# analog.net
KiCad netlist of a schematic drawn in EAGLE
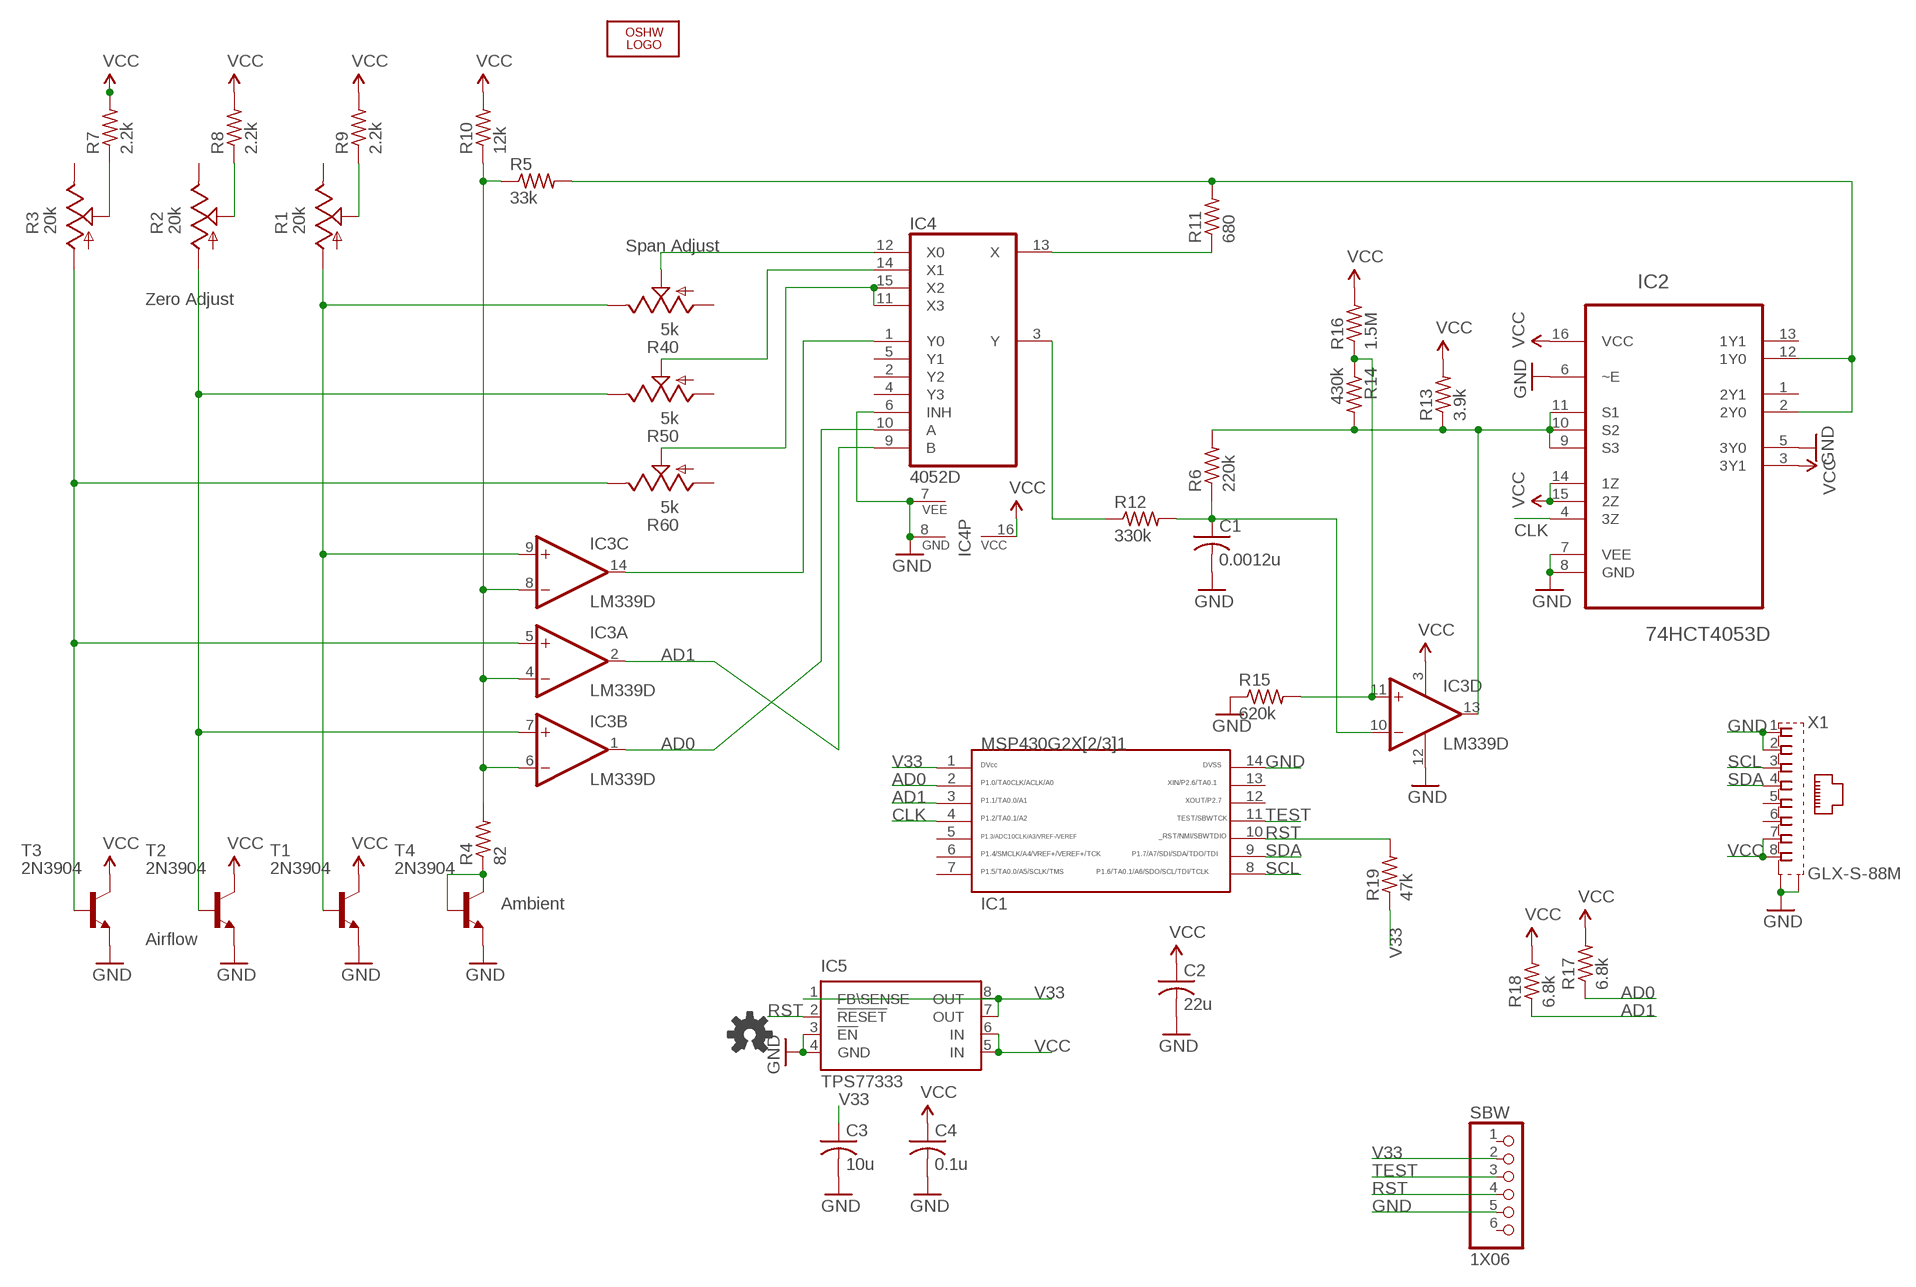
[diagram p0: schematic, sheet 1]

(export (version "E")
  (design (tool "Eeschema 10.0.6"))
  (components
    (comp (ref "C1")
      (value "0.0012u")
      (footprint "eagle-import:C0805")
      (libsource (lib "eagle-import") (part "C-USC0805"))
    )
    (comp (ref "C2")
      (value "22u")
      (footprint "eagle-import:C0805")
      (libsource (lib "eagle-import") (part "C-USC0805"))
    )
    (comp (ref "C3")
      (value "10u")
      (footprint "eagle-import:C0805")
      (libsource (lib "eagle-import") (part "C-USC0805"))
    )
    (comp (ref "C4")
      (value "0.1u")
      (footprint "eagle-import:C0805")
      (libsource (lib "eagle-import") (part "C-USC0805"))
    )
    (comp (ref "IC1")
      (value "G2X[2/3]1---PW14")
      (footprint "eagle-import:PW14")
      (libsource (lib "eagle-import") (part "G2X[2/3]1---PW14"))
    )
    (comp (ref "IC2")
      (value "74HCT4053D")
      (footprint "eagle-import:SOIC127P600X175-16N")
      (libsource (lib "eagle-import") (part "74HCT4053D"))
    )
    (comp (ref "IC3")
      (value "LM339D")
      (footprint "eagle-import:SO14")
      (libsource (lib "eagle-import") (part "LM339D"))
    )
    (comp (ref "IC4")
      (value "4052D")
      (footprint "eagle-import:SO16")
      (libsource (lib "eagle-import") (part "4052D"))
    )
    (comp (ref "IC5")
      (value "TPS77333")
      (footprint "eagle-import:TPS77333")
      (libsource (lib "eagle-import") (part "TPS77333"))
    )
    (comp (ref "LOGO1")
      (value "OSHW_LOGO_FILLX0150-NT")
      (footprint "eagle-import:OSHW_FILLX150_NOTEXT")
      (libsource (lib "eagle-import") (part "OSHW_LOGO_FILLX0150-NT"))
    )
    (comp (ref "R1")
      (value "20k")
      (footprint "eagle-import:SM-42_43W")
      (libsource (lib "eagle-import") (part "TRIM_US-SM-42/43W"))
    )
    (comp (ref "R2")
      (value "20k")
      (footprint "eagle-import:SM-42_43W")
      (libsource (lib "eagle-import") (part "TRIM_US-SM-42/43W"))
    )
    (comp (ref "R3")
      (value "20k")
      (footprint "eagle-import:SM-42_43W")
      (libsource (lib "eagle-import") (part "TRIM_US-SM-42/43W"))
    )
    (comp (ref "R4")
      (value "82")
      (footprint "eagle-import:M0805")
      (libsource (lib "eagle-import") (part "R-US_M0805"))
    )
    (comp (ref "R5")
      (value "33k")
      (footprint "eagle-import:R0805")
      (libsource (lib "eagle-import") (part "R-US_R0805"))
    )
    (comp (ref "R6")
      (value "220k")
      (footprint "eagle-import:R0805")
      (libsource (lib "eagle-import") (part "R-US_R0805"))
    )
    (comp (ref "R7")
      (value "2.2k")
      (footprint "eagle-import:M0805")
      (libsource (lib "eagle-import") (part "resistor_R-US_M0805"))
    )
    (comp (ref "R8")
      (value "2.2k")
      (footprint "eagle-import:R0805")
      (libsource (lib "eagle-import") (part "R-US_R0805"))
    )
    (comp (ref "R9")
      (value "2.2k")
      (footprint "eagle-import:R0805")
      (libsource (lib "eagle-import") (part "R-US_R0805"))
    )
    (comp (ref "R10")
      (value "12k")
      (footprint "eagle-import:R0805")
      (libsource (lib "eagle-import") (part "R-US_R0805"))
    )
    (comp (ref "R11")
      (value "680")
      (footprint "eagle-import:R0805")
      (libsource (lib "eagle-import") (part "R-US_R0805"))
    )
    (comp (ref "R12")
      (value "330k")
      (footprint "eagle-import:R0805")
      (libsource (lib "eagle-import") (part "R-US_R0805"))
    )
    (comp (ref "R13")
      (value "3.9k")
      (footprint "eagle-import:R0805")
      (libsource (lib "eagle-import") (part "R-US_R0805"))
    )
    (comp (ref "R14")
      (value "430k")
      (footprint "eagle-import:R0805")
      (libsource (lib "eagle-import") (part "R-US_R0805"))
    )
    (comp (ref "R15")
      (value "620k")
      (footprint "eagle-import:R0805")
      (libsource (lib "eagle-import") (part "R-US_R0805"))
    )
    (comp (ref "R16")
      (value "1.5M")
      (footprint "eagle-import:R0805")
      (libsource (lib "eagle-import") (part "R-US_R0805"))
    )
    (comp (ref "R17")
      (value "6.8k")
      (footprint "eagle-import:M0805")
      (libsource (lib "eagle-import") (part "R-US_M0805"))
    )
    (comp (ref "R18")
      (value "6.8k")
      (footprint "eagle-import:M0805")
      (libsource (lib "eagle-import") (part "R-US_M0805"))
    )
    (comp (ref "R19")
      (value "47k")
      (footprint "eagle-import:R0805")
      (libsource (lib "eagle-import") (part "R-US_R0805"))
    )
    (comp (ref "R40")
      (value "5k")
      (footprint "eagle-import:SM-42_43W")
      (libsource (lib "eagle-import") (part "TRIM_US-SM-42/43W"))
    )
    (comp (ref "R50")
      (value "5k")
      (footprint "eagle-import:SM-42_43W")
      (libsource (lib "eagle-import") (part "TRIM_US-SM-42/43W"))
    )
    (comp (ref "R60")
      (value "5k")
      (footprint "eagle-import:SM-42_43W")
      (libsource (lib "eagle-import") (part "TRIM_US-SM-42/43W"))
    )
    (comp (ref "SBW")
      (value "1X06")
      (footprint "eagle-import:1X06")
      (libsource (lib "eagle-import") (part "1X06"))
    )
    (comp (ref "T1")
      (value "2N3904")
      (footprint "eagle-import:TO92")
      (libsource (lib "eagle-import") (part "2N3904"))
    )
    (comp (ref "T2")
      (value "2N3904")
      (footprint "eagle-import:TO92")
      (libsource (lib "eagle-import") (part "2N3904"))
    )
    (comp (ref "T3")
      (value "2N3904")
      (footprint "eagle-import:TO92")
      (libsource (lib "eagle-import") (part "2N3904"))
    )
    (comp (ref "T4")
      (value "2N3904")
      (footprint "eagle-import:TO92")
      (libsource (lib "eagle-import") (part "2N3904"))
    )
    (comp (ref "X1")
      (value "GLX-S-88M")
      (footprint "eagle-import:GLX-S-88M")
      (libsource (lib "eagle-import") (part "GLX-S-88M"))
    )
  )
  (nets
    (net (code "1") (name "/AD0") (class "Default")
      (node (ref "IC1") (pin "2") (pinfunction "2_2") (pintype "bidirectional"))
      (node (ref "IC3") (pin "1") (pinfunction "OUT_1") (pintype "open_collector"))
      (node (ref "IC4") (pin "10") (pinfunction "A_10") (pintype "input"))
      (node (ref "R17") (pin "1") (pinfunction "1_1") (pintype "passive"))
    )
    (net (code "2") (name "/AD1") (class "Default")
      (node (ref "IC1") (pin "3") (pinfunction "3_3") (pintype "bidirectional"))
      (node (ref "IC3") (pin "2") (pinfunction "OUT_2") (pintype "open_collector"))
      (node (ref "IC4") (pin "9") (pinfunction "B_9") (pintype "input"))
      (node (ref "R18") (pin "1") (pinfunction "1_1") (pintype "passive"))
    )
    (net (code "3") (name "/CLK") (class "Default")
      (node (ref "IC1") (pin "4") (pinfunction "4_4") (pintype "bidirectional"))
      (node (ref "IC2") (pin "4") (pinfunction "3Z_4") (pintype "bidirectional"))
    )
    (net (code "4") (name "/RST") (class "Default")
      (node (ref "IC1") (pin "10") (pinfunction "10_10") (pintype "bidirectional"))
      (node (ref "IC5") (pin "2") (pinfunction "~{RESET}_2") (pintype "input"))
      (node (ref "R19") (pin "2") (pinfunction "2_2") (pintype "passive"))
      (node (ref "SBW") (pin "4") (pinfunction "4_4") (pintype "passive"))
    )
    (net (code "5") (name "/SCL") (class "Default")
      (node (ref "IC1") (pin "8") (pinfunction "8_8") (pintype "bidirectional"))
      (node (ref "X1") (pin "3") (pinfunction "3_3") (pintype "passive"))
    )
    (net (code "6") (name "/SDA") (class "Default")
      (node (ref "IC1") (pin "9") (pinfunction "9_9") (pintype "bidirectional"))
      (node (ref "X1") (pin "4") (pinfunction "4_4") (pintype "passive"))
    )
    (net (code "7") (name "/TEST") (class "Default")
      (node (ref "IC1") (pin "11") (pinfunction "11_11") (pintype "bidirectional"))
      (node (ref "SBW") (pin "3") (pinfunction "3_3") (pintype "passive"))
    )
    (net (code "8") (name "/V33") (class "Default")
      (node (ref "C3") (pin "1") (pinfunction "1_1") (pintype "passive"))
      (node (ref "IC1") (pin "1") (pinfunction "1_1") (pintype "bidirectional"))
      (node (ref "IC5") (pin "1") (pinfunction "FB\\SENSE_1") (pintype "input"))
      (node (ref "IC5") (pin "7") (pinfunction "OUT_7") (pintype "output"))
      (node (ref "IC5") (pin "8") (pinfunction "OUT_8") (pintype "passive"))
      (node (ref "R19") (pin "1") (pinfunction "1_1") (pintype "passive"))
      (node (ref "SBW") (pin "2") (pinfunction "2_2") (pintype "passive"))
    )
    (net (code "9") (name "GND") (class "Default")
      (node (ref "C1") (pin "2") (pinfunction "2_2") (pintype "passive"))
      (node (ref "C2") (pin "2") (pinfunction "2_2") (pintype "passive"))
      (node (ref "C3") (pin "2") (pinfunction "2_2") (pintype "passive"))
      (node (ref "C4") (pin "2") (pinfunction "2_2") (pintype "passive"))
      (node (ref "IC1") (pin "14") (pinfunction "14_14") (pintype "bidirectional"))
      (node (ref "IC2") (pin "5") (pinfunction "3Y0_5") (pintype "bidirectional"))
      (node (ref "IC2") (pin "6") (pinfunction "~{E}_6") (pintype "input"))
      (node (ref "IC2") (pin "7") (pinfunction "VEE_7") (pintype "power_in"))
      (node (ref "IC2") (pin "8") (pinfunction "GND_8") (pintype "passive"))
      (node (ref "IC3") (pin "12") (pinfunction "GND_12") (pintype "power_in"))
      (node (ref "IC4") (pin "6") (pinfunction "INH_6") (pintype "input"))
      (node (ref "IC4") (pin "7") (pinfunction "VEE_7") (pintype "power_in"))
      (node (ref "IC4") (pin "8") (pinfunction "GND_8") (pintype "power_in"))
      (node (ref "IC5") (pin "3") (pinfunction "~{EN}_3") (pintype "input"))
      (node (ref "IC5") (pin "4") (pinfunction "GND_4") (pintype "power_in"))
      (node (ref "R15") (pin "1") (pinfunction "1_1") (pintype "passive"))
      (node (ref "SBW") (pin "5") (pinfunction "5_5") (pintype "passive"))
      (node (ref "T1") (pin "3") (pinfunction "E_3") (pintype "passive"))
      (node (ref "T2") (pin "3") (pinfunction "E_3") (pintype "passive"))
      (node (ref "T3") (pin "3") (pinfunction "E_3") (pintype "passive"))
      (node (ref "T4") (pin "3") (pinfunction "E_3") (pintype "passive"))
      (node (ref "X1") (pin "1") (pinfunction "1_1") (pintype "passive"))
      (node (ref "X1") (pin "2") (pinfunction "2_2") (pintype "passive"))
      (node (ref "X1") (pin "S1") (pinfunction "S1_S1") (pintype "passive"))
      (node (ref "X1") (pin "S2") (pinfunction "S2_S2") (pintype "passive"))
    )
    (net (code "10") (name "Net-(IC2-1Y0)") (class "Default")
      (node (ref "IC2") (pin "12") (pinfunction "1Y0_12") (pintype "bidirectional"))
      (node (ref "IC2") (pin "2") (pinfunction "2Y0_2") (pintype "bidirectional"))
      (node (ref "R11") (pin "2") (pinfunction "2_2") (pintype "passive"))
      (node (ref "R5") (pin "2") (pinfunction "2_2") (pintype "passive"))
    )
    (net (code "11") (name "Net-(IC2-S1)") (class "Default")
      (node (ref "IC2") (pin "10") (pinfunction "S2_10") (pintype "input"))
      (node (ref "IC2") (pin "11") (pinfunction "S1_11") (pintype "input"))
      (node (ref "IC2") (pin "9") (pinfunction "S3_9") (pintype "input"))
      (node (ref "IC3") (pin "13") (pinfunction "OUT_13") (pintype "open_collector"))
      (node (ref "R13") (pin "1") (pinfunction "1_1") (pintype "passive"))
      (node (ref "R14") (pin "2") (pinfunction "2_2") (pintype "passive"))
      (node (ref "R6") (pin "2") (pinfunction "2_2") (pintype "passive"))
    )
    (net (code "12") (name "Net-(IC3A-+IN)") (class "Default")
      (node (ref "IC3") (pin "5") (pinfunction "+IN_5") (pintype "input"))
      (node (ref "R3") (pin "1") (pinfunction "A_1") (pintype "passive"))
      (node (ref "R60") (pin "3") (pinfunction "E_3") (pintype "passive"))
      (node (ref "T3") (pin "2") (pinfunction "B_2") (pintype "passive"))
    )
    (net (code "13") (name "Net-(IC3A--IN)") (class "Default")
      (node (ref "IC3") (pin "4") (pinfunction "-IN_4") (pintype "input"))
      (node (ref "IC3") (pin "6") (pinfunction "-IN_6") (pintype "input"))
      (node (ref "IC3") (pin "8") (pinfunction "-IN_8") (pintype "input"))
      (node (ref "R10") (pin "1") (pinfunction "1_1") (pintype "passive"))
      (node (ref "R4") (pin "2") (pinfunction "2_2") (pintype "passive"))
      (node (ref "R5") (pin "1") (pinfunction "1_1") (pintype "passive"))
    )
    (net (code "14") (name "Net-(IC3B-+IN)") (class "Default")
      (node (ref "IC3") (pin "7") (pinfunction "+IN_7") (pintype "input"))
      (node (ref "R2") (pin "1") (pinfunction "A_1") (pintype "passive"))
      (node (ref "R50") (pin "3") (pinfunction "E_3") (pintype "passive"))
      (node (ref "T2") (pin "2") (pinfunction "B_2") (pintype "passive"))
    )
    (net (code "15") (name "Net-(IC3C-+IN)") (class "Default")
      (node (ref "IC3") (pin "9") (pinfunction "+IN_9") (pintype "input"))
      (node (ref "R1") (pin "1") (pinfunction "A_1") (pintype "passive"))
      (node (ref "R40") (pin "3") (pinfunction "E_3") (pintype "passive"))
      (node (ref "T1") (pin "2") (pinfunction "B_2") (pintype "passive"))
    )
    (net (code "16") (name "Net-(IC3C-OUT)") (class "Default")
      (node (ref "IC3") (pin "14") (pinfunction "OUT_14") (pintype "open_collector"))
      (node (ref "IC4") (pin "1") (pinfunction "Y0_1") (pintype "bidirectional"))
    )
    (net (code "17") (name "Net-(IC3D-+IN)") (class "Default")
      (node (ref "IC3") (pin "11") (pinfunction "+IN_11") (pintype "input"))
      (node (ref "R14") (pin "1") (pinfunction "1_1") (pintype "passive"))
      (node (ref "R15") (pin "2") (pinfunction "2_2") (pintype "passive"))
      (node (ref "R16") (pin "1") (pinfunction "1_1") (pintype "passive"))
    )
    (net (code "18") (name "Net-(IC3D--IN)") (class "Default")
      (node (ref "C1") (pin "1") (pinfunction "1_1") (pintype "passive"))
      (node (ref "IC3") (pin "10") (pinfunction "-IN_10") (pintype "input"))
      (node (ref "R12") (pin "2") (pinfunction "2_2") (pintype "passive"))
      (node (ref "R6") (pin "1") (pinfunction "1_1") (pintype "passive"))
    )
    (net (code "19") (name "Net-(IC4A-X)") (class "Default")
      (node (ref "IC4") (pin "13") (pinfunction "X_13") (pintype "bidirectional"))
      (node (ref "R11") (pin "1") (pinfunction "1_1") (pintype "passive"))
    )
    (net (code "20") (name "Net-(IC4A-X0)") (class "Default")
      (node (ref "IC4") (pin "12") (pinfunction "X0_12") (pintype "bidirectional"))
      (node (ref "R40") (pin "2") (pinfunction "S_2") (pintype "passive"))
    )
    (net (code "21") (name "Net-(IC4A-X1)") (class "Default")
      (node (ref "IC4") (pin "14") (pinfunction "X1_14") (pintype "bidirectional"))
      (node (ref "R50") (pin "2") (pinfunction "S_2") (pintype "passive"))
    )
    (net (code "22") (name "Net-(IC4A-X2)") (class "Default")
      (node (ref "IC4") (pin "11") (pinfunction "X3_11") (pintype "bidirectional"))
      (node (ref "IC4") (pin "15") (pinfunction "X2_15") (pintype "bidirectional"))
      (node (ref "R60") (pin "2") (pinfunction "S_2") (pintype "passive"))
    )
    (net (code "23") (name "Net-(IC4A-Y)") (class "Default")
      (node (ref "IC4") (pin "3") (pinfunction "Y_3") (pintype "bidirectional"))
      (node (ref "R12") (pin "1") (pinfunction "1_1") (pintype "passive"))
    )
    (net (code "24") (name "Net-(R1-S)") (class "Default")
      (node (ref "R1") (pin "2") (pinfunction "S_2") (pintype "passive"))
      (node (ref "R9") (pin "1") (pinfunction "1_1") (pintype "passive"))
    )
    (net (code "25") (name "Net-(R2-S)") (class "Default")
      (node (ref "R2") (pin "2") (pinfunction "S_2") (pintype "passive"))
      (node (ref "R8") (pin "1") (pinfunction "1_1") (pintype "passive"))
    )
    (net (code "26") (name "Net-(R3-S)") (class "Default")
      (node (ref "R3") (pin "2") (pinfunction "S_2") (pintype "passive"))
      (node (ref "R7") (pin "1") (pinfunction "1_1") (pintype "passive"))
    )
    (net (code "27") (name "Net-(T4-B)") (class "Default")
      (node (ref "R4") (pin "1") (pinfunction "1_1") (pintype "passive"))
      (node (ref "T4") (pin "1") (pinfunction "C_1") (pintype "passive"))
      (node (ref "T4") (pin "2") (pinfunction "B_2") (pintype "passive"))
    )
    (net (code "28") (name "VCC") (class "Default")
      (node (ref "C2") (pin "1") (pinfunction "1_1") (pintype "passive"))
      (node (ref "C4") (pin "1") (pinfunction "1_1") (pintype "passive"))
      (node (ref "IC2") (pin "14") (pinfunction "1Z_14") (pintype "bidirectional"))
      (node (ref "IC2") (pin "15") (pinfunction "2Z_15") (pintype "bidirectional"))
      (node (ref "IC2") (pin "16") (pinfunction "VCC_16") (pintype "power_in"))
      (node (ref "IC2") (pin "3") (pinfunction "3Y1_3") (pintype "bidirectional"))
      (node (ref "IC3") (pin "3") (pinfunction "V+_3") (pintype "power_in"))
      (node (ref "IC4") (pin "16") (pinfunction "VCC_16") (pintype "power_in"))
      (node (ref "IC5") (pin "5") (pinfunction "IN_5") (pintype "input"))
      (node (ref "IC5") (pin "6") (pinfunction "IN_6") (pintype "input"))
      (node (ref "R10") (pin "2") (pinfunction "2_2") (pintype "passive"))
      (node (ref "R13") (pin "2") (pinfunction "2_2") (pintype "passive"))
      (node (ref "R16") (pin "2") (pinfunction "2_2") (pintype "passive"))
      (node (ref "R17") (pin "2") (pinfunction "2_2") (pintype "passive"))
      (node (ref "R18") (pin "2") (pinfunction "2_2") (pintype "passive"))
      (node (ref "R7") (pin "2") (pinfunction "2_2") (pintype "passive"))
      (node (ref "R8") (pin "2") (pinfunction "2_2") (pintype "passive"))
      (node (ref "R9") (pin "2") (pinfunction "2_2") (pintype "passive"))
      (node (ref "T1") (pin "1") (pinfunction "C_1") (pintype "passive"))
      (node (ref "T2") (pin "1") (pinfunction "C_1") (pintype "passive"))
      (node (ref "T3") (pin "1") (pinfunction "C_1") (pintype "passive"))
      (node (ref "X1") (pin "7") (pinfunction "7_7") (pintype "passive"))
      (node (ref "X1") (pin "8") (pinfunction "8_8") (pintype "passive"))
    )
    (net (code "29") (name "unconnected-(IC1-Pad5)") (class "Default")
      (node (ref "IC1") (pin "5") (pinfunction "5_5") (pintype "bidirectional"))
    )
    (net (code "30") (name "unconnected-(IC1-Pad6)") (class "Default")
      (node (ref "IC1") (pin "6") (pinfunction "6_6") (pintype "bidirectional"))
    )
    (net (code "31") (name "unconnected-(IC1-Pad7)") (class "Default")
      (node (ref "IC1") (pin "7") (pinfunction "7_7") (pintype "bidirectional"))
    )
    (net (code "32") (name "unconnected-(IC1-Pad12)") (class "Default")
      (node (ref "IC1") (pin "12") (pinfunction "12_12") (pintype "bidirectional"))
    )
    (net (code "33") (name "unconnected-(IC1-Pad13)") (class "Default")
      (node (ref "IC1") (pin "13") (pinfunction "13_13") (pintype "bidirectional"))
    )
    (net (code "34") (name "unconnected-(IC2-1Y1-Pad13)") (class "Default")
      (node (ref "IC2") (pin "13") (pinfunction "1Y1_13") (pintype "bidirectional"))
    )
    (net (code "35") (name "unconnected-(IC2-2Y1-Pad1)") (class "Default")
      (node (ref "IC2") (pin "1") (pinfunction "2Y1_1") (pintype "bidirectional"))
    )
    (net (code "36") (name "unconnected-(IC4A-Y1-Pad5)") (class "Default")
      (node (ref "IC4") (pin "5") (pinfunction "Y1_5") (pintype "bidirectional"))
    )
    (net (code "37") (name "unconnected-(IC4A-Y2-Pad2)") (class "Default")
      (node (ref "IC4") (pin "2") (pinfunction "Y2_2") (pintype "bidirectional"))
    )
    (net (code "38") (name "unconnected-(IC4A-Y3-Pad4)") (class "Default")
      (node (ref "IC4") (pin "4") (pinfunction "Y3_4") (pintype "bidirectional"))
    )
    (net (code "39") (name "unconnected-(R1-E-Pad3)") (class "Default")
      (node (ref "R1") (pin "3") (pinfunction "E_3") (pintype "passive"))
    )
    (net (code "40") (name "unconnected-(R2-E-Pad3)") (class "Default")
      (node (ref "R2") (pin "3") (pinfunction "E_3") (pintype "passive"))
    )
    (net (code "41") (name "unconnected-(R3-E-Pad3)") (class "Default")
      (node (ref "R3") (pin "3") (pinfunction "E_3") (pintype "passive"))
    )
    (net (code "42") (name "unconnected-(R40-A-Pad1)") (class "Default")
      (node (ref "R40") (pin "1") (pinfunction "A_1") (pintype "passive"))
    )
    (net (code "43") (name "unconnected-(R50-A-Pad1)") (class "Default")
      (node (ref "R50") (pin "1") (pinfunction "A_1") (pintype "passive"))
    )
    (net (code "44") (name "unconnected-(R60-A-Pad1)") (class "Default")
      (node (ref "R60") (pin "1") (pinfunction "A_1") (pintype "passive"))
    )
    (net (code "45") (name "unconnected-(SBW-Pad1)") (class "Default")
      (node (ref "SBW") (pin "1") (pinfunction "1_1") (pintype "passive"))
    )
    (net (code "46") (name "unconnected-(SBW-Pad6)") (class "Default")
      (node (ref "SBW") (pin "6") (pinfunction "6_6") (pintype "passive"))
    )
    (net (code "47") (name "unconnected-(X1-Pad5)") (class "Default")
      (node (ref "X1") (pin "5") (pinfunction "5_5") (pintype "passive"))
    )
    (net (code "48") (name "unconnected-(X1-Pad6)") (class "Default")
      (node (ref "X1") (pin "6") (pinfunction "6_6") (pintype "passive"))
    )
  )
)
